# LEDs_FMU_REV_1B.net
KiCad netlist of a schematic drawn in Altium Designer
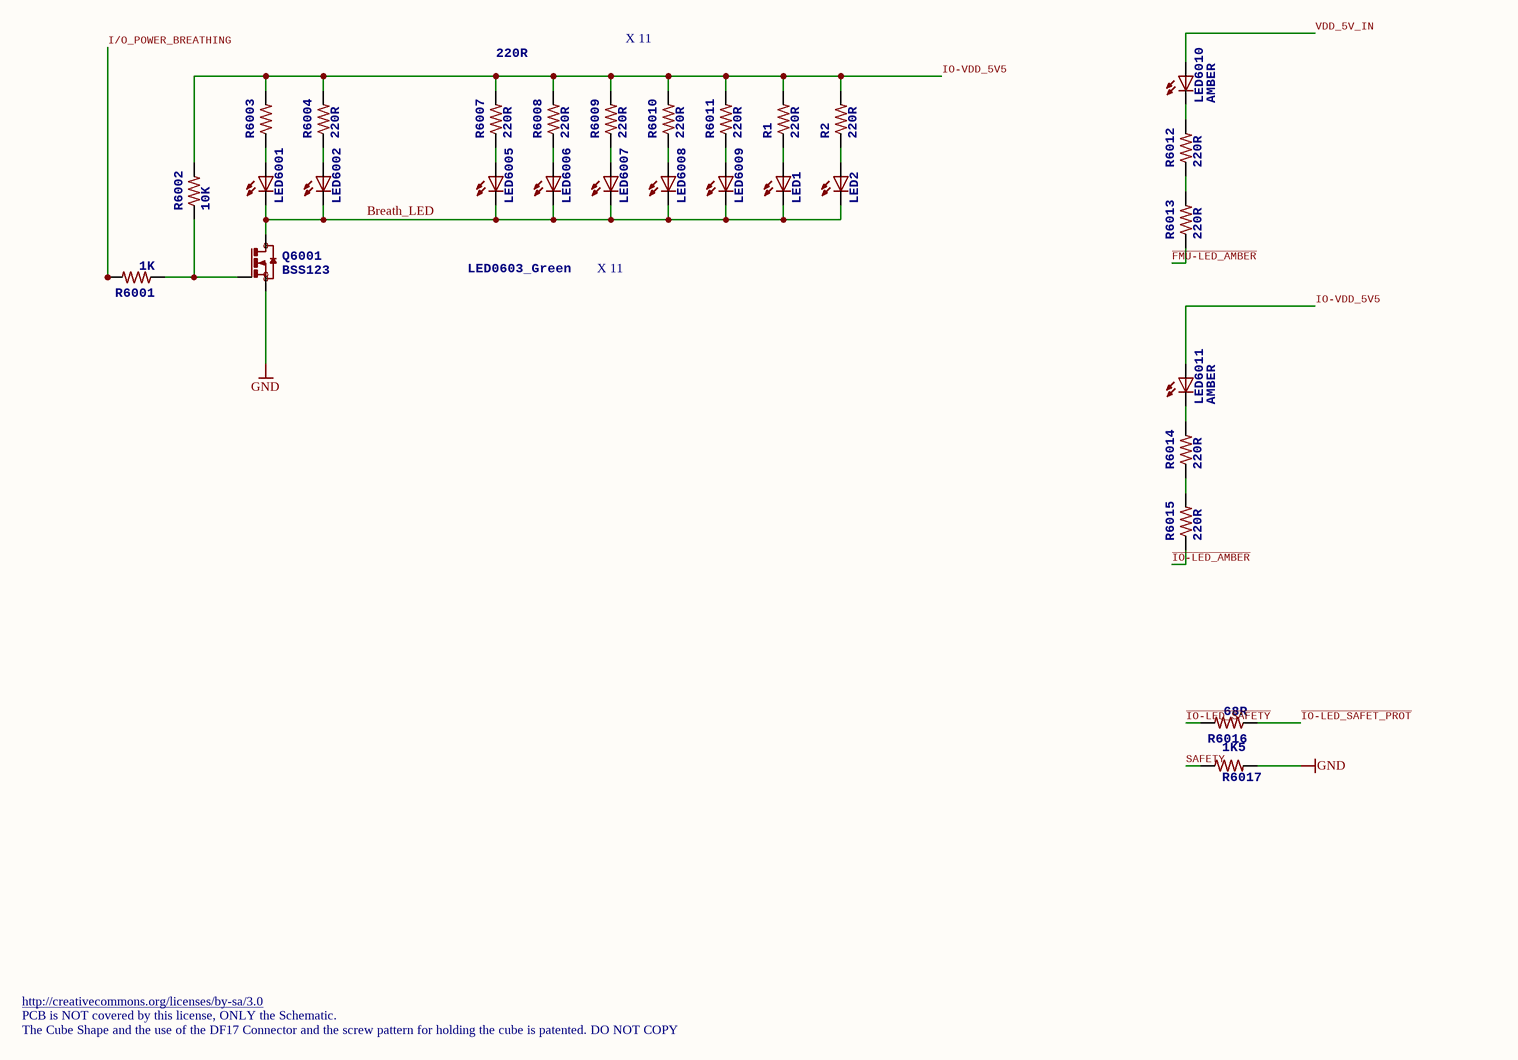
[diagram p0: LEDs_FMU_REV_1B.SchDoc]

(export (version "E")
  (design (tool "Eeschema 10.0.6"))
  (components
    (comp (ref "LED1")
      (value "LED0603_Green")
      (footprint "0603-LED-Blue")
      (description "LED GREEN ROUND CLEAR SMD")
      (libsource (lib "pixhawk2") (part "LED0603_Blue"))
    )
    (comp (ref "LED2")
      (value "LED0603_Green")
      (footprint "0603-LED-Blue")
      (description "LED GREEN ROUND CLEAR SMD")
      (libsource (lib "pixhawk2") (part "LED0603_Blue"))
    )
    (comp (ref "LED6001")
      (value "LED0603_Green")
      (footprint "0603-LED-Blue")
      (description "LED GREEN ROUND CLEAR SMD")
      (libsource (lib "pixhawk2") (part "LED0603_Blue"))
    )
    (comp (ref "LED6002")
      (value "LED0603_Green")
      (footprint "0603-LED-Blue")
      (description "LED GREEN ROUND CLEAR SMD")
      (libsource (lib "pixhawk2") (part "LED0603_Blue"))
    )
    (comp (ref "LED6005")
      (value "LED0603_Green")
      (footprint "0603-LED-Blue")
      (description "LED GREEN ROUND CLEAR SMD")
      (libsource (lib "pixhawk2") (part "LED0603_Blue"))
    )
    (comp (ref "LED6006")
      (value "LED0603_Green")
      (footprint "0603-LED-Blue")
      (description "LED GREEN ROUND CLEAR SMD")
      (libsource (lib "pixhawk2") (part "LED0603_Blue"))
    )
    (comp (ref "LED6007")
      (value "LED0603_Green")
      (footprint "0603-LED-Blue")
      (description "LED GREEN ROUND CLEAR SMD")
      (libsource (lib "pixhawk2") (part "LED0603_Blue"))
    )
    (comp (ref "LED6008")
      (value "LED0603_Green")
      (footprint "0603-LED-Blue")
      (description "LED GREEN ROUND CLEAR SMD")
      (libsource (lib "pixhawk2") (part "LED0603_Blue"))
    )
    (comp (ref "LED6009")
      (value "LED0603_Green")
      (footprint "0603-LED-Blue")
      (description "LED GREEN ROUND CLEAR SMD")
      (libsource (lib "pixhawk2") (part "LED0603_Blue"))
    )
    (comp (ref "LED6010")
      (value "AMBER")
      (footprint "0603-LED")
      (description "LED 1.6X0.8 DOME ORN CLEAR SMD")
      (libsource (lib "pixhawk2") (part "LED0603"))
    )
    (comp (ref "LED6011")
      (value "AMBER")
      (footprint "0603-LED")
      (description "LED 1.6X0.8 DOME ORN CLEAR SMD")
      (libsource (lib "pixhawk2") (part "LED0603"))
    )
    (comp (ref "Q6001")
      (value "BSS123")
      (footprint "SOT23")
      (description "MOSFET N-CH 100V 170MA SOT23-3")
      (libsource (lib "transistor-small-signal") (part "BSS123"))
    )
    (comp (ref "R1")
      (value "220R")
      (footprint "0402-RES")
      (description "RES 220 OHM 1/16W 1% 0402 SMD")
      (libsource (lib "pixhawk2") (part "RESISTOR0402-RES"))
    )
    (comp (ref "R2")
      (value "220R")
      (footprint "0402-RES")
      (description "RES 220 OHM 1/16W 1% 0402 SMD")
      (libsource (lib "pixhawk2") (part "RESISTOR0402-RES"))
    )
    (comp (ref "R6001")
      (value "1K")
      (footprint "0402-RES")
      (description "RES 1K OHM 1/16W 1% 0402")
      (libsource (lib "pixhawk2") (part "RESISTOR0402-RES"))
    )
    (comp (ref "R6002")
      (value "10K")
      (footprint "0402-RES")
      (description "RES 10K OHM 1/16W 1% 0402 SMD")
      (libsource (lib "pixhawk2") (part "RESISTOR0402-RES"))
    )
    (comp (ref "R6003")
      (value "220R")
      (footprint "0402-RES")
      (description "RES 220 OHM 1/16W 1% 0402 SMD")
      (libsource (lib "pixhawk2") (part "RESISTOR0402-RES"))
    )
    (comp (ref "R6004")
      (value "220R")
      (footprint "0402-RES")
      (description "RES 220 OHM 1/16W 1% 0402 SMD")
      (libsource (lib "pixhawk2") (part "RESISTOR0402-RES"))
    )
    (comp (ref "R6007")
      (value "220R")
      (footprint "0402-RES")
      (description "RES 220 OHM 1/16W 1% 0402 SMD")
      (libsource (lib "pixhawk2") (part "RESISTOR0402-RES"))
    )
    (comp (ref "R6008")
      (value "220R")
      (footprint "0402-RES")
      (description "RES 220 OHM 1/16W 1% 0402 SMD")
      (libsource (lib "pixhawk2") (part "RESISTOR0402-RES"))
    )
    (comp (ref "R6009")
      (value "220R")
      (footprint "0402-RES")
      (description "RES 220 OHM 1/16W 1% 0402 SMD")
      (libsource (lib "pixhawk2") (part "RESISTOR0402-RES"))
    )
    (comp (ref "R6010")
      (value "220R")
      (footprint "0402-RES")
      (description "RES 220 OHM 1/16W 1% 0402 SMD")
      (libsource (lib "pixhawk2") (part "RESISTOR0402-RES"))
    )
    (comp (ref "R6011")
      (value "220R")
      (footprint "0402-RES")
      (description "RES 220 OHM 1/16W 1% 0402 SMD")
      (libsource (lib "pixhawk2") (part "RESISTOR0402-RES"))
    )
    (comp (ref "R6012")
      (value "220R")
      (footprint "0402-RES")
      (description "RES 220 OHM 1/16W 1% 0402 SMD")
      (libsource (lib "pixhawk2") (part "RESISTOR0402-RES"))
    )
    (comp (ref "R6013")
      (value "220R")
      (footprint "0402-RES")
      (description "RES 220 OHM 1/16W 1% 0402 SMD")
      (libsource (lib "pixhawk2") (part "RESISTOR0402-RES"))
    )
    (comp (ref "R6014")
      (value "220R")
      (footprint "0402-RES")
      (description "RES 220 OHM 1/16W 1% 0402 SMD")
      (libsource (lib "pixhawk2") (part "RESISTOR0402-RES"))
    )
    (comp (ref "R6015")
      (value "220R")
      (footprint "0402-RES")
      (description "RES 220 OHM 1/16W 1% 0402 SMD")
      (libsource (lib "pixhawk2") (part "RESISTOR0402-RES"))
    )
    (comp (ref "R6016")
      (value "68R")
      (footprint "0402-RES")
      (description "Thick Film Resistors - SMD 0402 68ohms 5% Tol")
      (libsource (lib "pixhawk2") (part "RESISTOR0402-RES"))
    )
    (comp (ref "R6017")
      (value "1K5")
      (footprint "0402-RES")
      (description "RES 1.5K OHM 1/16W 1% 0402 SMD")
      (libsource (lib "pixhawk2") (part "RESISTOR0402-RES"))
    )
  )
  (nets
    (net (code "1") (name "/Breath_LED") (class "Default")
      (node (ref "LED1") (pin "C") (pinfunction "C_C") (pintype "passive"))
      (node (ref "LED2") (pin "C") (pinfunction "C_C") (pintype "passive"))
      (node (ref "LED6001") (pin "C") (pinfunction "C_C") (pintype "passive"))
      (node (ref "LED6002") (pin "C") (pinfunction "C_C") (pintype "passive"))
      (node (ref "LED6005") (pin "C") (pinfunction "C_C") (pintype "passive"))
      (node (ref "LED6006") (pin "C") (pinfunction "C_C") (pintype "passive"))
      (node (ref "LED6007") (pin "C") (pinfunction "C_C") (pintype "passive"))
      (node (ref "LED6008") (pin "C") (pinfunction "C_C") (pintype "passive"))
      (node (ref "LED6009") (pin "C") (pinfunction "C_C") (pintype "passive"))
      (node (ref "Q6001") (pin "3") (pinfunction "D_3") (pintype "passive"))
    )
    (net (code "2") (name "/IO-VDD_5V5") (class "Default")
      (node (ref "LED6011") (pin "A") (pinfunction "A_A") (pintype "passive"))
      (node (ref "R1") (pin "P$2") (pinfunction "2_P$2") (pintype "passive"))
      (node (ref "R2") (pin "P$2") (pinfunction "2_P$2") (pintype "passive"))
      (node (ref "R6002") (pin "P$2") (pinfunction "2_P$2") (pintype "passive"))
      (node (ref "R6003") (pin "P$2") (pinfunction "2_P$2") (pintype "passive"))
      (node (ref "R6004") (pin "P$2") (pinfunction "2_P$2") (pintype "passive"))
      (node (ref "R6007") (pin "P$2") (pinfunction "2_P$2") (pintype "passive"))
      (node (ref "R6008") (pin "P$2") (pinfunction "2_P$2") (pintype "passive"))
      (node (ref "R6009") (pin "P$2") (pinfunction "2_P$2") (pintype "passive"))
      (node (ref "R6010") (pin "P$2") (pinfunction "2_P$2") (pintype "passive"))
      (node (ref "R6011") (pin "P$2") (pinfunction "2_P$2") (pintype "passive"))
    )
    (net (code "3") (name "/I{slash}O_POWER_BREATHING") (class "Default")
      (node (ref "R6001") (pin "P$2") (pinfunction "2_P$2") (pintype "passive"))
    )
    (net (code "4") (name "/SAFETY") (class "Default")
      (node (ref "R6017") (pin "P$1") (pinfunction "1_P$1") (pintype "passive"))
    )
    (net (code "5") (name "/VDD_5V_IN") (class "Default")
      (node (ref "LED6010") (pin "A") (pinfunction "A_A") (pintype "passive"))
    )
    (net (code "6") (name "/~{FMU-LED_AMBER}") (class "Default")
      (node (ref "R6013") (pin "P$1") (pinfunction "1_P$1") (pintype "passive"))
    )
    (net (code "7") (name "/~{IO-LED_AMBER}") (class "Default")
      (node (ref "R6015") (pin "P$1") (pinfunction "1_P$1") (pintype "passive"))
    )
    (net (code "8") (name "/~{IO-LED_SAFETY}") (class "Default")
      (node (ref "R6016") (pin "P$2") (pinfunction "2_P$2") (pintype "passive"))
    )
    (net (code "9") (name "/~{IO-LED_SAFET_PROT}") (class "Default")
      (node (ref "R6016") (pin "P$1") (pinfunction "1_P$1") (pintype "passive"))
    )
    (net (code "10") (name "GND") (class "Default")
      (node (ref "Q6001") (pin "2") (pinfunction "S_2") (pintype "passive"))
      (node (ref "R6017") (pin "P$2") (pinfunction "2_P$2") (pintype "passive"))
    )
    (net (code "11") (name "Net-(Q6001-G)") (class "Default")
      (node (ref "Q6001") (pin "1") (pinfunction "G_1") (pintype "passive"))
      (node (ref "R6001") (pin "P$1") (pinfunction "1_P$1") (pintype "passive"))
      (node (ref "R6002") (pin "P$1") (pinfunction "1_P$1") (pintype "passive"))
    )
    (net (code "12") (name "Net-(R1-1)") (class "Default")
      (node (ref "LED1") (pin "A") (pinfunction "A_A") (pintype "passive"))
      (node (ref "R1") (pin "P$1") (pinfunction "1_P$1") (pintype "passive"))
    )
    (net (code "13") (name "Net-(R2-1)") (class "Default")
      (node (ref "LED2") (pin "A") (pinfunction "A_A") (pintype "passive"))
      (node (ref "R2") (pin "P$1") (pinfunction "1_P$1") (pintype "passive"))
    )
    (net (code "14") (name "Net-(R6003-1)") (class "Default")
      (node (ref "LED6001") (pin "A") (pinfunction "A_A") (pintype "passive"))
      (node (ref "R6003") (pin "P$1") (pinfunction "1_P$1") (pintype "passive"))
    )
    (net (code "15") (name "Net-(R6004-1)") (class "Default")
      (node (ref "LED6002") (pin "A") (pinfunction "A_A") (pintype "passive"))
      (node (ref "R6004") (pin "P$1") (pinfunction "1_P$1") (pintype "passive"))
    )
    (net (code "16") (name "Net-(R6007-1)") (class "Default")
      (node (ref "LED6005") (pin "A") (pinfunction "A_A") (pintype "passive"))
      (node (ref "R6007") (pin "P$1") (pinfunction "1_P$1") (pintype "passive"))
    )
    (net (code "17") (name "Net-(R6008-1)") (class "Default")
      (node (ref "LED6006") (pin "A") (pinfunction "A_A") (pintype "passive"))
      (node (ref "R6008") (pin "P$1") (pinfunction "1_P$1") (pintype "passive"))
    )
    (net (code "18") (name "Net-(R6009-1)") (class "Default")
      (node (ref "LED6007") (pin "A") (pinfunction "A_A") (pintype "passive"))
      (node (ref "R6009") (pin "P$1") (pinfunction "1_P$1") (pintype "passive"))
    )
    (net (code "19") (name "Net-(R6010-1)") (class "Default")
      (node (ref "LED6008") (pin "A") (pinfunction "A_A") (pintype "passive"))
      (node (ref "R6010") (pin "P$1") (pinfunction "1_P$1") (pintype "passive"))
    )
    (net (code "20") (name "Net-(R6011-1)") (class "Default")
      (node (ref "LED6009") (pin "A") (pinfunction "A_A") (pintype "passive"))
      (node (ref "R6011") (pin "P$1") (pinfunction "1_P$1") (pintype "passive"))
    )
    (net (code "21") (name "Net-(R6012-1)") (class "Default")
      (node (ref "R6012") (pin "P$1") (pinfunction "1_P$1") (pintype "passive"))
      (node (ref "R6013") (pin "P$2") (pinfunction "2_P$2") (pintype "passive"))
    )
    (net (code "22") (name "Net-(R6012-2)") (class "Default")
      (node (ref "LED6010") (pin "C") (pinfunction "C_C") (pintype "passive"))
      (node (ref "R6012") (pin "P$2") (pinfunction "2_P$2") (pintype "passive"))
    )
    (net (code "23") (name "Net-(R6014-1)") (class "Default")
      (node (ref "R6014") (pin "P$1") (pinfunction "1_P$1") (pintype "passive"))
      (node (ref "R6015") (pin "P$2") (pinfunction "2_P$2") (pintype "passive"))
    )
    (net (code "24") (name "Net-(R6014-2)") (class "Default")
      (node (ref "LED6011") (pin "C") (pinfunction "C_C") (pintype "passive"))
      (node (ref "R6014") (pin "P$2") (pinfunction "2_P$2") (pintype "passive"))
    )
  )
)
